# Power_-_LDO.net
KiCad netlist of a schematic drawn in Altium Designer
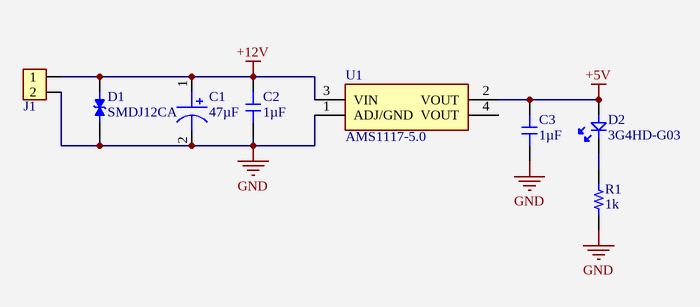
[diagram p0: Power - LDO.SchDoc]

(export (version "E")
  (design (tool "Eeschema 10.0.6"))
  (components
    (comp (ref "C1")
      (value "47µF")
      (footprint "CAP_63x11x25")
      (description "CAP.EL.47uF 50V 6.3x11 2.5MM 105C TB KOSHIN")
      (libsource (lib "MainLibrary") (part "PKRM-050V470ME110-T2.5"))
    )
    (comp (ref "C2")
      (value "1µF")
      (footprint "0805")
      (description "MLCC (2012) 0805 1uF 50VDC ±10% X7R")
      (libsource (lib "MainLibrary") (part "CC0805KKX7R9BB105"))
    )
    (comp (ref "C3")
      (value "1µF")
      (footprint "0805")
      (description "MLCC (2012) 0805 1uF 50VDC ±10% X7R")
      (libsource (lib "MainLibrary") (part "CC0805KKX7R9BB105"))
    )
    (comp (ref "D1")
      (value "SMDJ12CA")
      (footprint "MainLibrary:DIOM6859X262N")
      (description "150.8A 14.7V 12V SMC ESD and Surge Protection (TVS/ESD) ROHS")
      (fields (field (name "MP") "SMDJ36CA"))
      (libsource (lib "MainLibrary") (part "SMDJ12CA"))
    )
    (comp (ref "D2")
      (value "3G4HD-G03")
      (footprint "LED_SSL-LX4673GD-LA20")
      (description "LED 3MM GREEN 20mcd 45° GREEN/DIFFUSED")
      (fields
        (field (name "MANUFACTURER_PART_NUMBER") "LTST-C190KRKT")
        (field (name "MOUSER PART NUMBER") "859-LTST-C190KRKT")
      )
      (libsource (lib "MainLibrary") (part "3G4HD-G03"))
    )
    (comp (ref "J1")
      (value "691322310002")
      (footprint "WURTH_3_81_691322310002")
      (description "WURTH 3.81MM Terminal Block 691322310002")
      (libsource (lib "MainLibrary") (part "691322310002"))
    )
    (comp (ref "R1")
      (value "1k")
      (footprint "0402_RES")
      (description "RES.(1005) 0402 1K Ohms 1% 1/16W 100PPM AEC-Q200 S")
      (libsource (lib "MainLibrary") (part "AC0402FR-071KL"))
    )
    (comp (ref "U1")
      (value "AMS1117-5.0")
      (footprint "SOT229P700X180-4N")
      (description "1A LOW DROPOUT VOLTAGE REGULATOR SOT-223")
      (fields (field (name "MP") "AMS1117") (field (name "MF") "Advanced Monolithic Systems"))
      (libsource (lib "MainLibrary") (part "AMS1117-5.0"))
    )
  )
  (nets
    (net (code "1") (name "+5V") (class "Default")
      (node (ref "C3") (pin "2") (pinfunction "2_2") (pintype "passive"))
      (node (ref "D2") (pin "A") (pinfunction "A_A") (pintype "passive"))
      (node (ref "U1") (pin "2") (pinfunction "VOUT_2") (pintype "passive"))
    )
    (net (code "2") (name "+12V") (class "Default")
      (node (ref "C1") (pin "1") (pinfunction "+_1") (pintype "passive"))
      (node (ref "C2") (pin "2") (pinfunction "2_2") (pintype "passive"))
      (node (ref "D1") (pin "2") (pinfunction "2_2") (pintype "passive"))
      (node (ref "J1") (pin "1") (pinfunction "1_1") (pintype "passive"))
      (node (ref "U1") (pin "3") (pinfunction "VIN_3") (pintype "passive"))
    )
    (net (code "3") (name "GND") (class "Default")
      (node (ref "C1") (pin "2") (pinfunction "-_2") (pintype "passive"))
      (node (ref "C2") (pin "1") (pinfunction "1_1") (pintype "passive"))
      (node (ref "C3") (pin "1") (pinfunction "1_1") (pintype "passive"))
      (node (ref "D1") (pin "1") (pinfunction "1_1") (pintype "passive"))
      (node (ref "J1") (pin "2") (pinfunction "2_2") (pintype "passive"))
      (node (ref "R1") (pin "1") (pinfunction "1_1") (pintype "passive"))
      (node (ref "U1") (pin "1") (pinfunction "ADJ/GND_1") (pintype "power_in"))
    )
    (net (code "4") (name "Net-(D2-PadC)") (class "Default")
      (node (ref "D2") (pin "C") (pinfunction "C_C") (pintype "passive"))
      (node (ref "R1") (pin "2") (pinfunction "2_2") (pintype "passive"))
    )
    (net (code "5") (name "unconnected-(U1-VOUT-Pad4)") (class "Default")
      (node (ref "U1") (pin "4") (pinfunction "VOUT_4") (pintype "passive"))
    )
  )
)
